# ECU_AutoRC_ACC_SERVO_r00.net
KiCad netlist of a schematic drawn in Altium Designer
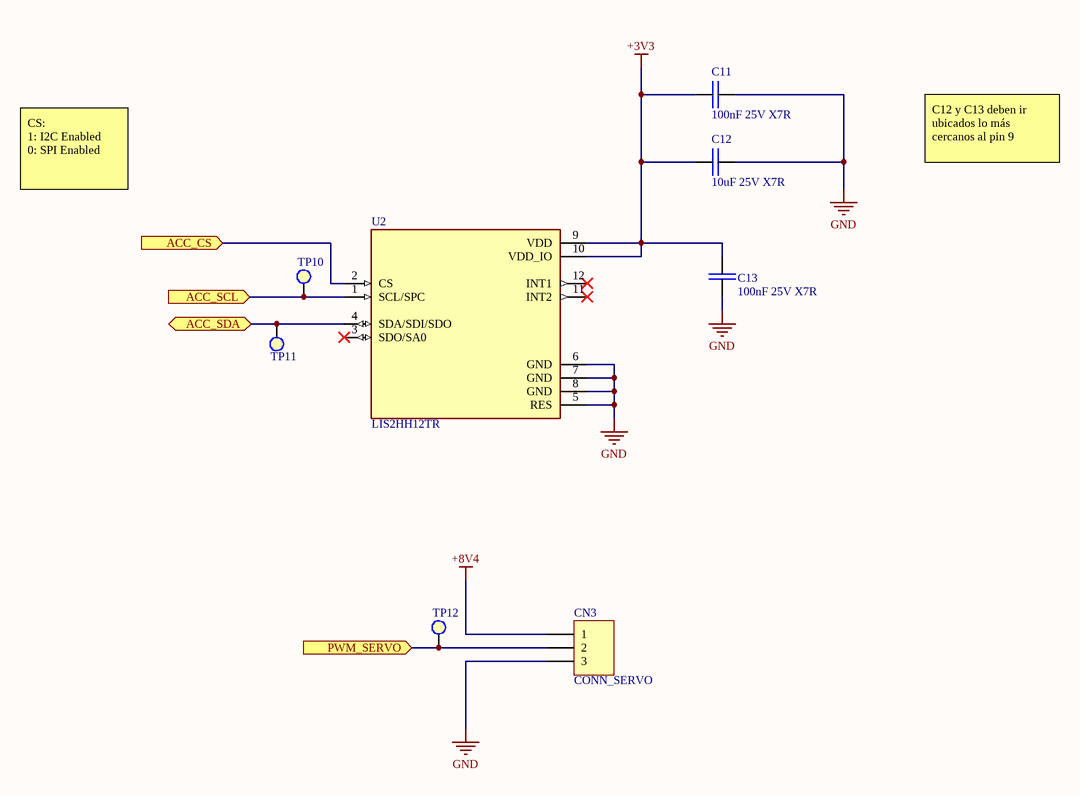
[diagram p0: ECU_AutoRC_ACC_SERVO_r00.SchDoc]

(export (version "E")
  (design (tool "Eeschema 10.0.6"))
  (components
    (comp (ref "C11")
      (value "100nF 25V X7R")
      (footprint "C_0805")
      (description "Non Polarizated Capacitor")
      (libsource (lib "ECU_AutoRC_r00") (part "Capacitor NP"))
    )
    (comp (ref "C12")
      (value "10uF 25V X7R")
      (footprint "C_1206")
      (description "Non Polarizated Capacitor")
      (libsource (lib "ECU_AutoRC_r00") (part "Capacitor NP"))
    )
    (comp (ref "C13")
      (value "100nF 25V X7R")
      (footprint "C_0805")
      (description "Non Polarizated Capacitor")
      (libsource (lib "ECU_AutoRC_r00") (part "Capacitor NP"))
    )
    (comp (ref "CN3")
      (value "CONN_SERVO")
      (footprint "HEADER_M_1X3_2.5MM")
      (description "3 Pin Connector")
      (libsource (lib "ECU_AutoRC_r00") (part "CONN_03P"))
    )
    (comp (ref "TP10")
      (value "Test Point")
      (footprint "TEST_POINT")
      (libsource (lib "ECU_AutoRC_r00") (part "TestPoint"))
    )
    (comp (ref "TP11")
      (value "Test Point")
      (footprint "TEST_POINT")
      (libsource (lib "ECU_AutoRC_r00") (part "TestPoint"))
    )
    (comp (ref "TP12")
      (value "Test Point")
      (footprint "TEST_POINT")
      (libsource (lib "ECU_AutoRC_r00") (part "TestPoint"))
    )
    (comp (ref "U2")
      (value "LIS2HH12TR")
      (footprint "PQFN50P200X200X100-12N")
      (description "Accelerometer X, Y, Z Axis Â±2g, 4g, 8g 5Hz ~ 400Hz 12-LGA _2x2_")
      (fields (field (name "MF") "STMicroelectronics"))
      (libsource (lib "ECU_AutoRC_r00") (part "LIS2HH12TR"))
    )
  )
  (nets
    (net (code "1") (name "+3V3") (class "Default")
      (node (ref "C11") (pin "1") (pinfunction "1_1") (pintype "passive"))
      (node (ref "C12") (pin "1") (pinfunction "1_1") (pintype "passive"))
      (node (ref "C13") (pin "1") (pinfunction "1_1") (pintype "passive"))
      (node (ref "U2") (pin "10") (pinfunction "VDD_IO_10") (pintype "power_in"))
      (node (ref "U2") (pin "9") (pinfunction "VDD_9") (pintype "power_in"))
    )
    (net (code "2") (name "+8V4") (class "Default")
      (node (ref "CN3") (pin "1") (pinfunction "1_1") (pintype "passive"))
    )
    (net (code "3") (name "/ACC_CS") (class "Default")
      (node (ref "U2") (pin "2") (pinfunction "CS_2") (pintype "input"))
    )
    (net (code "4") (name "/ACC_SCL") (class "Default")
      (node (ref "TP10") (pin "1") (pintype "passive"))
      (node (ref "U2") (pin "1") (pinfunction "SCL/SPC_1") (pintype "input"))
    )
    (net (code "5") (name "/ACC_SDA") (class "Default")
      (node (ref "TP11") (pin "1") (pintype "passive"))
      (node (ref "U2") (pin "4") (pinfunction "SDA/SDI/SDO_4") (pintype "bidirectional"))
    )
    (net (code "6") (name "/PWM_SERVO") (class "Default")
      (node (ref "CN3") (pin "2") (pinfunction "2_2") (pintype "passive"))
      (node (ref "TP12") (pin "1") (pintype "passive"))
    )
    (net (code "7") (name "GND") (class "Default")
      (node (ref "C11") (pin "2") (pinfunction "2_2") (pintype "passive"))
      (node (ref "C12") (pin "2") (pinfunction "2_2") (pintype "passive"))
      (node (ref "C13") (pin "2") (pinfunction "2_2") (pintype "passive"))
      (node (ref "CN3") (pin "3") (pinfunction "3_3") (pintype "passive"))
      (node (ref "U2") (pin "5") (pinfunction "RES_5") (pintype "power_in"))
      (node (ref "U2") (pin "6") (pinfunction "GND_6") (pintype "power_in"))
      (node (ref "U2") (pin "7") (pinfunction "GND_7") (pintype "power_in"))
      (node (ref "U2") (pin "8") (pinfunction "GND_8") (pintype "power_in"))
    )
    (net (code "8") (name "unconnected-(U2-INT1-Pad12)") (class "Default")
      (node (ref "U2") (pin "12") (pinfunction "INT1_12") (pintype "output+no_connect"))
    )
    (net (code "9") (name "unconnected-(U2-INT2-Pad11)") (class "Default")
      (node (ref "U2") (pin "11") (pinfunction "INT2_11") (pintype "output+no_connect"))
    )
    (net (code "10") (name "unconnected-(U2-SDO{slash}SA0-Pad3)") (class "Default")
      (node (ref "U2") (pin "3") (pinfunction "SDO/SA0_3") (pintype "bidirectional+no_connect"))
    )
  )
)
